# Keyglove_Kit_v0_2.net
KiCad netlist of a schematic drawn in EAGLE
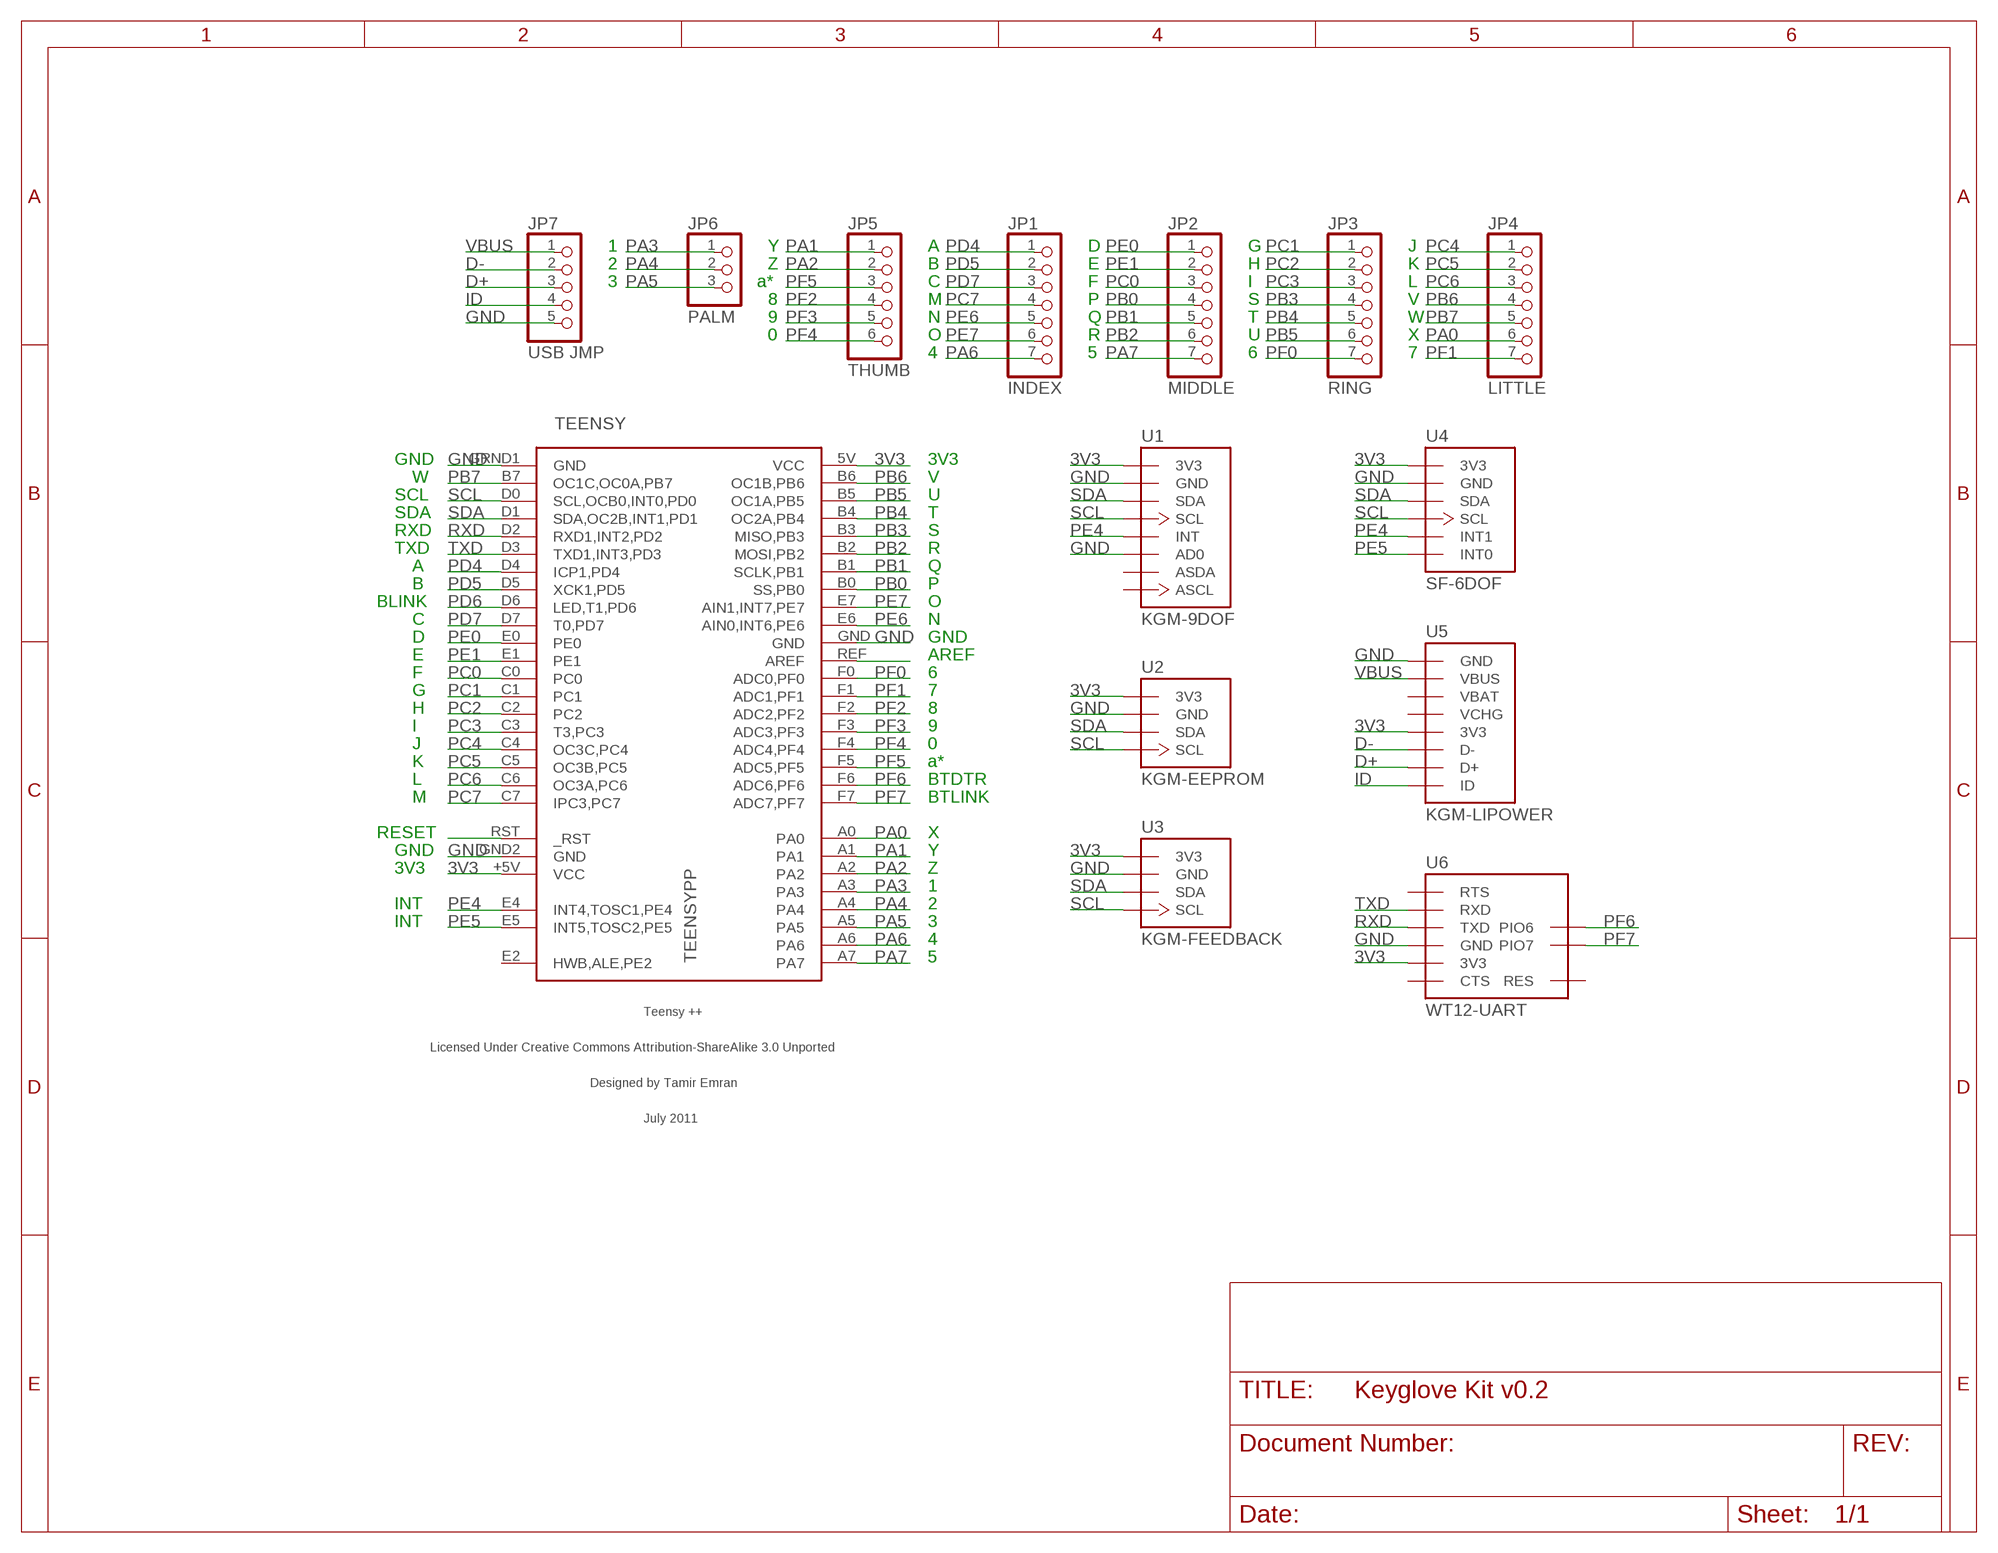
[diagram p0: schematic, sheet 1]

(export (version "E")
  (design (tool "Eeschema 10.0.6"))
  (components
    (comp (ref "JP1")
      (value "INDEX")
      (footprint "eagle-import:1X07")
      (libsource (lib "eagle-import") (part "PINHD-1X7"))
    )
    (comp (ref "JP2")
      (value "MIDDLE")
      (footprint "eagle-import:1X07")
      (libsource (lib "eagle-import") (part "PINHD-1X7"))
    )
    (comp (ref "JP3")
      (value "RING")
      (footprint "eagle-import:1X07")
      (libsource (lib "eagle-import") (part "PINHD-1X7"))
    )
    (comp (ref "JP4")
      (value "LITTLE")
      (footprint "eagle-import:1X07")
      (libsource (lib "eagle-import") (part "PINHD-1X7"))
    )
    (comp (ref "JP5")
      (value "THUMB")
      (footprint "eagle-import:1X06")
      (libsource (lib "eagle-import") (part "PINHD-1X6"))
    )
    (comp (ref "JP6")
      (value "PALM")
      (footprint "eagle-import:1X03")
      (libsource (lib "eagle-import") (part "PINHD-1X3"))
    )
    (comp (ref "JP7")
      (value "USB JMP")
      (footprint "eagle-import:1X05")
      (libsource (lib "eagle-import") (part "PINHD-1X5"))
    )
    (comp (ref "TEENSY")
      (value "TEENSYPP")
      (footprint "eagle-import:TEENSYPP")
      (libsource (lib "eagle-import") (part "TEENSYPP"))
    )
    (comp (ref "U1")
      (value "KGM-9DOF")
      (footprint "eagle-import:KGM-9DOF")
      (libsource (lib "eagle-import") (part "KGM-9DOF"))
    )
    (comp (ref "U2")
      (value "KGM-EEPROM")
      (footprint "eagle-import:KGM-EEPROM")
      (libsource (lib "eagle-import") (part "KGM-EEPROM"))
    )
    (comp (ref "U3")
      (value "KGM-FEEDBACK")
      (footprint "eagle-import:KGM-FEEDBACK")
      (libsource (lib "eagle-import") (part "KGM-FEEDBACK"))
    )
    (comp (ref "U4")
      (value "SF-6DOF")
      (footprint "eagle-import:SF-6DOF")
      (libsource (lib "eagle-import") (part "SF-6DOF"))
    )
    (comp (ref "U5")
      (value "KGM-LIPOWER")
      (footprint "eagle-import:KGM-LIPOWER")
      (libsource (lib "eagle-import") (part "KGM-LIPOWER"))
    )
    (comp (ref "U6")
      (value "WT12-UART")
      (footprint "eagle-import:WT12-UART")
      (libsource (lib "eagle-import") (part "WT12-UART"))
    )
  )
  (nets
    (net (code "1") (name "/3V3") (class "Default")
      (node (ref "TEENSY") (pin "+5V") (pinfunction "VCC_+5V") (pintype "power_in"))
      (node (ref "TEENSY") (pin "5V") (pinfunction "VCC_5V") (pintype "power_in"))
      (node (ref "U1") (pin "3V3") (pinfunction "3V3_3V3") (pintype "power_in"))
      (node (ref "U2") (pin "3V3") (pinfunction "3V3_3V3") (pintype "power_in"))
      (node (ref "U3") (pin "3V3") (pinfunction "3V3_3V3") (pintype "power_in"))
      (node (ref "U4") (pin "3V3") (pinfunction "3V3_3V3") (pintype "power_in"))
      (node (ref "U5") (pin "3V3") (pinfunction "3V3_3V3") (pintype "power_in"))
      (node (ref "U6") (pin "3V3") (pinfunction "3V3_3V3") (pintype "power_in"))
    )
    (net (code "2") (name "/D+") (class "Default")
      (node (ref "JP7") (pin "3") (pinfunction "3_3") (pintype "passive"))
      (node (ref "U5") (pin "D+") (pinfunction "D+_D+") (pintype "bidirectional"))
    )
    (net (code "3") (name "/D-") (class "Default")
      (node (ref "JP7") (pin "2") (pinfunction "2_2") (pintype "passive"))
      (node (ref "U5") (pin "D-") (pinfunction "D-_D-") (pintype "bidirectional"))
    )
    (net (code "4") (name "/GND") (class "Default")
      (node (ref "JP7") (pin "5") (pinfunction "5_5") (pintype "passive"))
      (node (ref "TEENSY") (pin "GND") (pinfunction "GND_GND") (pintype "power_in"))
      (node (ref "TEENSY") (pin "GND2") (pinfunction "GND_GND2") (pintype "power_in"))
      (node (ref "TEENSY") (pin "GRND1") (pinfunction "GND_GRND1") (pintype "power_in"))
      (node (ref "U1") (pin "AD0") (pinfunction "AD0_AD0") (pintype "input"))
      (node (ref "U1") (pin "GND") (pinfunction "GND_GND") (pintype "power_in"))
      (node (ref "U2") (pin "GND") (pinfunction "GND_GND") (pintype "power_in"))
      (node (ref "U3") (pin "GND") (pinfunction "GND_GND") (pintype "power_in"))
      (node (ref "U4") (pin "GND") (pinfunction "GND_GND") (pintype "power_in"))
      (node (ref "U5") (pin "GND") (pinfunction "GND_GND") (pintype "power_in"))
      (node (ref "U6") (pin "GND") (pinfunction "GND_GND") (pintype "power_in"))
    )
    (net (code "5") (name "/ID") (class "Default")
      (node (ref "JP7") (pin "4") (pinfunction "4_4") (pintype "passive"))
      (node (ref "U5") (pin "ID") (pinfunction "ID_ID") (pintype "bidirectional"))
    )
    (net (code "6") (name "/PA0") (class "Default")
      (node (ref "JP4") (pin "6") (pinfunction "6_6") (pintype "passive"))
      (node (ref "TEENSY") (pin "A0") (pinfunction "PA0_A0") (pintype "bidirectional"))
    )
    (net (code "7") (name "/PA1") (class "Default")
      (node (ref "JP5") (pin "1") (pinfunction "1_1") (pintype "passive"))
      (node (ref "TEENSY") (pin "A1") (pinfunction "PA1_A1") (pintype "bidirectional"))
    )
    (net (code "8") (name "/PA2") (class "Default")
      (node (ref "JP5") (pin "2") (pinfunction "2_2") (pintype "passive"))
      (node (ref "TEENSY") (pin "A2") (pinfunction "PA2_A2") (pintype "bidirectional"))
    )
    (net (code "9") (name "/PA3") (class "Default")
      (node (ref "JP6") (pin "1") (pinfunction "1_1") (pintype "passive"))
      (node (ref "TEENSY") (pin "A3") (pinfunction "PA3_A3") (pintype "bidirectional"))
    )
    (net (code "10") (name "/PA4") (class "Default")
      (node (ref "JP6") (pin "2") (pinfunction "2_2") (pintype "passive"))
      (node (ref "TEENSY") (pin "A4") (pinfunction "PA4_A4") (pintype "bidirectional"))
    )
    (net (code "11") (name "/PA5") (class "Default")
      (node (ref "JP6") (pin "3") (pinfunction "3_3") (pintype "passive"))
      (node (ref "TEENSY") (pin "A5") (pinfunction "PA5_A5") (pintype "bidirectional"))
    )
    (net (code "12") (name "/PA6") (class "Default")
      (node (ref "JP1") (pin "7") (pinfunction "7_7") (pintype "passive"))
      (node (ref "TEENSY") (pin "A6") (pinfunction "PA6_A6") (pintype "bidirectional"))
    )
    (net (code "13") (name "/PA7") (class "Default")
      (node (ref "JP2") (pin "7") (pinfunction "7_7") (pintype "passive"))
      (node (ref "TEENSY") (pin "A7") (pinfunction "PA7_A7") (pintype "bidirectional"))
    )
    (net (code "14") (name "/PB0") (class "Default")
      (node (ref "JP2") (pin "4") (pinfunction "4_4") (pintype "passive"))
      (node (ref "TEENSY") (pin "B0") (pinfunction "SS,PB0_B0") (pintype "bidirectional"))
    )
    (net (code "15") (name "/PB1") (class "Default")
      (node (ref "JP2") (pin "5") (pinfunction "5_5") (pintype "passive"))
      (node (ref "TEENSY") (pin "B1") (pinfunction "SCLK,PB1_B1") (pintype "bidirectional"))
    )
    (net (code "16") (name "/PB2") (class "Default")
      (node (ref "JP2") (pin "6") (pinfunction "6_6") (pintype "passive"))
      (node (ref "TEENSY") (pin "B2") (pinfunction "MOSI,PB2_B2") (pintype "bidirectional"))
    )
    (net (code "17") (name "/PB3") (class "Default")
      (node (ref "JP3") (pin "4") (pinfunction "4_4") (pintype "passive"))
      (node (ref "TEENSY") (pin "B3") (pinfunction "MISO,PB3_B3") (pintype "bidirectional"))
    )
    (net (code "18") (name "/PB4") (class "Default")
      (node (ref "JP3") (pin "5") (pinfunction "5_5") (pintype "passive"))
      (node (ref "TEENSY") (pin "B4") (pinfunction "OC2A,PB4_B4") (pintype "bidirectional"))
    )
    (net (code "19") (name "/PB5") (class "Default")
      (node (ref "JP3") (pin "6") (pinfunction "6_6") (pintype "passive"))
      (node (ref "TEENSY") (pin "B5") (pinfunction "OC1A,PB5_B5") (pintype "bidirectional"))
    )
    (net (code "20") (name "/PB6") (class "Default")
      (node (ref "JP4") (pin "4") (pinfunction "4_4") (pintype "passive"))
      (node (ref "TEENSY") (pin "B6") (pinfunction "OC1B,PB6_B6") (pintype "bidirectional"))
    )
    (net (code "21") (name "/PB7") (class "Default")
      (node (ref "JP4") (pin "5") (pinfunction "5_5") (pintype "passive"))
      (node (ref "TEENSY") (pin "B7") (pinfunction "OC1C,OC0A,PB7_B7") (pintype "bidirectional"))
    )
    (net (code "22") (name "/PC0") (class "Default")
      (node (ref "JP2") (pin "3") (pinfunction "3_3") (pintype "passive"))
      (node (ref "TEENSY") (pin "C0") (pinfunction "PC0_C0") (pintype "bidirectional"))
    )
    (net (code "23") (name "/PC1") (class "Default")
      (node (ref "JP3") (pin "1") (pinfunction "1_1") (pintype "passive"))
      (node (ref "TEENSY") (pin "C1") (pinfunction "PC1_C1") (pintype "bidirectional"))
    )
    (net (code "24") (name "/PC2") (class "Default")
      (node (ref "JP3") (pin "2") (pinfunction "2_2") (pintype "passive"))
      (node (ref "TEENSY") (pin "C2") (pinfunction "PC2_C2") (pintype "bidirectional"))
    )
    (net (code "25") (name "/PC3") (class "Default")
      (node (ref "JP3") (pin "3") (pinfunction "3_3") (pintype "passive"))
      (node (ref "TEENSY") (pin "C3") (pinfunction "T3,PC3_C3") (pintype "bidirectional"))
    )
    (net (code "26") (name "/PC4") (class "Default")
      (node (ref "JP4") (pin "1") (pinfunction "1_1") (pintype "passive"))
      (node (ref "TEENSY") (pin "C4") (pinfunction "OC3C,PC4_C4") (pintype "bidirectional"))
    )
    (net (code "27") (name "/PC5") (class "Default")
      (node (ref "JP4") (pin "2") (pinfunction "2_2") (pintype "passive"))
      (node (ref "TEENSY") (pin "C5") (pinfunction "OC3B,PC5_C5") (pintype "bidirectional"))
    )
    (net (code "28") (name "/PC6") (class "Default")
      (node (ref "JP4") (pin "3") (pinfunction "3_3") (pintype "passive"))
      (node (ref "TEENSY") (pin "C6") (pinfunction "OC3A,PC6_C6") (pintype "bidirectional"))
    )
    (net (code "29") (name "/PC7") (class "Default")
      (node (ref "JP1") (pin "4") (pinfunction "4_4") (pintype "passive"))
      (node (ref "TEENSY") (pin "C7") (pinfunction "IPC3,PC7_C7") (pintype "bidirectional"))
    )
    (net (code "30") (name "/PD4") (class "Default")
      (node (ref "JP1") (pin "1") (pinfunction "1_1") (pintype "passive"))
      (node (ref "TEENSY") (pin "D4") (pinfunction "ICP1,PD4_D4") (pintype "bidirectional"))
    )
    (net (code "31") (name "/PD5") (class "Default")
      (node (ref "JP1") (pin "2") (pinfunction "2_2") (pintype "passive"))
      (node (ref "TEENSY") (pin "D5") (pinfunction "XCK1,PD5_D5") (pintype "bidirectional"))
    )
    (net (code "32") (name "/PD6") (class "Default")
      (node (ref "TEENSY") (pin "D6") (pinfunction "LED,T1,PD6_D6") (pintype "bidirectional"))
    )
    (net (code "33") (name "/PD7") (class "Default")
      (node (ref "JP1") (pin "3") (pinfunction "3_3") (pintype "passive"))
      (node (ref "TEENSY") (pin "D7") (pinfunction "T0,PD7_D7") (pintype "bidirectional"))
    )
    (net (code "34") (name "/PE0") (class "Default")
      (node (ref "JP2") (pin "1") (pinfunction "1_1") (pintype "passive"))
      (node (ref "TEENSY") (pin "E0") (pinfunction "PE0_E0") (pintype "bidirectional"))
    )
    (net (code "35") (name "/PE1") (class "Default")
      (node (ref "JP2") (pin "2") (pinfunction "2_2") (pintype "passive"))
      (node (ref "TEENSY") (pin "E1") (pinfunction "PE1_E1") (pintype "bidirectional"))
    )
    (net (code "36") (name "/PE4") (class "Default")
      (node (ref "TEENSY") (pin "E4") (pinfunction "INT4,TOSC1,PE4_E4") (pintype "bidirectional"))
      (node (ref "U1") (pin "INT") (pinfunction "INT_INT") (pintype "output"))
      (node (ref "U4") (pin "INT1") (pinfunction "INT1_INT1") (pintype "output"))
    )
    (net (code "37") (name "/PE5") (class "Default")
      (node (ref "TEENSY") (pin "E5") (pinfunction "INT5,TOSC2,PE5_E5") (pintype "bidirectional"))
      (node (ref "U4") (pin "INT0") (pinfunction "INT0_INT0") (pintype "output"))
    )
    (net (code "38") (name "/PE6") (class "Default")
      (node (ref "JP1") (pin "5") (pinfunction "5_5") (pintype "passive"))
      (node (ref "TEENSY") (pin "E6") (pinfunction "AIN0,INT6,PE6_E6") (pintype "bidirectional"))
    )
    (net (code "39") (name "/PE7") (class "Default")
      (node (ref "JP1") (pin "6") (pinfunction "6_6") (pintype "passive"))
      (node (ref "TEENSY") (pin "E7") (pinfunction "AIN1,INT7,PE7_E7") (pintype "bidirectional"))
    )
    (net (code "40") (name "/PF0") (class "Default")
      (node (ref "JP3") (pin "7") (pinfunction "7_7") (pintype "passive"))
      (node (ref "TEENSY") (pin "F0") (pinfunction "ADC0,PF0_F0") (pintype "bidirectional"))
    )
    (net (code "41") (name "/PF1") (class "Default")
      (node (ref "JP4") (pin "7") (pinfunction "7_7") (pintype "passive"))
      (node (ref "TEENSY") (pin "F1") (pinfunction "ADC1,PF1_F1") (pintype "bidirectional"))
    )
    (net (code "42") (name "/PF2") (class "Default")
      (node (ref "JP5") (pin "4") (pinfunction "4_4") (pintype "passive"))
      (node (ref "TEENSY") (pin "F2") (pinfunction "ADC2,PF2_F2") (pintype "bidirectional"))
    )
    (net (code "43") (name "/PF3") (class "Default")
      (node (ref "JP5") (pin "5") (pinfunction "5_5") (pintype "passive"))
      (node (ref "TEENSY") (pin "F3") (pinfunction "ADC3,PF3_F3") (pintype "bidirectional"))
    )
    (net (code "44") (name "/PF4") (class "Default")
      (node (ref "JP5") (pin "6") (pinfunction "6_6") (pintype "passive"))
      (node (ref "TEENSY") (pin "F4") (pinfunction "ADC4,PF4_F4") (pintype "bidirectional"))
    )
    (net (code "45") (name "/PF5") (class "Default")
      (node (ref "JP5") (pin "3") (pinfunction "3_3") (pintype "passive"))
      (node (ref "TEENSY") (pin "F5") (pinfunction "ADC5,PF5_F5") (pintype "bidirectional"))
    )
    (net (code "46") (name "/PF6") (class "Default")
      (node (ref "TEENSY") (pin "F6") (pinfunction "ADC6,PF6_F6") (pintype "bidirectional"))
      (node (ref "U6") (pin "PIO6") (pinfunction "PIO6_PIO6") (pintype "bidirectional"))
    )
    (net (code "47") (name "/PF7") (class "Default")
      (node (ref "TEENSY") (pin "F7") (pinfunction "ADC7,PF7_F7") (pintype "bidirectional"))
      (node (ref "U6") (pin "PIO7") (pinfunction "PIO7_PIO7") (pintype "bidirectional"))
    )
    (net (code "48") (name "/RXD") (class "Default")
      (node (ref "TEENSY") (pin "D2") (pinfunction "RXD1,INT2,PD2_D2") (pintype "bidirectional"))
      (node (ref "U6") (pin "TXD") (pinfunction "TXD_TXD") (pintype "output"))
    )
    (net (code "49") (name "/SCL") (class "Default")
      (node (ref "TEENSY") (pin "D0") (pinfunction "SCL,OCB0,INT0,PD0_D0") (pintype "bidirectional"))
      (node (ref "U1") (pin "SCL") (pinfunction "SCL_SCL") (pintype "bidirectional"))
      (node (ref "U2") (pin "SCL") (pinfunction "SCL_SCL") (pintype "bidirectional"))
      (node (ref "U3") (pin "SCL") (pinfunction "SCL_SCL") (pintype "bidirectional"))
      (node (ref "U4") (pin "SCL") (pinfunction "SCL_SCL") (pintype "bidirectional"))
    )
    (net (code "50") (name "/SDA") (class "Default")
      (node (ref "TEENSY") (pin "D1") (pinfunction "SDA,OC2B,INT1,PD1_D1") (pintype "bidirectional"))
      (node (ref "U1") (pin "SDA") (pinfunction "SDA_SDA") (pintype "bidirectional"))
      (node (ref "U2") (pin "SDA") (pinfunction "SDA_SDA") (pintype "bidirectional"))
      (node (ref "U3") (pin "SDA") (pinfunction "SDA_SDA") (pintype "bidirectional"))
      (node (ref "U4") (pin "SDA") (pinfunction "SDA_SDA") (pintype "bidirectional"))
    )
    (net (code "51") (name "/TXD") (class "Default")
      (node (ref "TEENSY") (pin "D3") (pinfunction "TXD1,INT3,PD3_D3") (pintype "bidirectional"))
      (node (ref "U6") (pin "RXD") (pinfunction "RXD_RXD") (pintype "input"))
    )
    (net (code "52") (name "/VBAT") (class "Default")
      (node (ref "U5") (pin "VBAT") (pinfunction "VBAT_VBAT") (pintype "power_in"))
    )
    (net (code "53") (name "/VBUS") (class "Default")
      (node (ref "JP7") (pin "1") (pinfunction "1_1") (pintype "passive"))
      (node (ref "U5") (pin "VBUS") (pinfunction "VBUS_VBUS") (pintype "power_in"))
    )
    (net (code "54") (name "/VCHG") (class "Default")
      (node (ref "U5") (pin "VCHG") (pinfunction "VCHG_VCHG") (pintype "power_in"))
    )
    (net (code "55") (name "unconnected-(TEENSY-AREF-PadREF)") (class "Default")
      (node (ref "TEENSY") (pin "REF") (pinfunction "AREF_REF") (pintype "input"))
    )
    (net (code "56") (name "unconnected-(TEENSY-HWB,ALE,PE2-PadE2)") (class "Default")
      (node (ref "TEENSY") (pin "E2") (pinfunction "HWB,ALE,PE2_E2") (pintype "bidirectional"))
    )
    (net (code "57") (name "unconnected-(TEENSY-_RST-PadRST)") (class "Default")
      (node (ref "TEENSY") (pin "RST") (pinfunction "_RST_RST") (pintype "input"))
    )
    (net (code "58") (name "unconnected-(U1-PadASCL)") (class "Default")
      (node (ref "U1") (pin "ASCL") (pinfunction "ASCL_ASCL") (pintype "bidirectional"))
    )
    (net (code "59") (name "unconnected-(U1-PadASDA)") (class "Default")
      (node (ref "U1") (pin "ASDA") (pinfunction "ASDA_ASDA") (pintype "bidirectional"))
    )
    (net (code "60") (name "unconnected-(U6-PadCTS)") (class "Default")
      (node (ref "U6") (pin "CTS") (pinfunction "CTS_CTS") (pintype "input"))
    )
    (net (code "61") (name "unconnected-(U6-PadRTS)") (class "Default")
      (node (ref "U6") (pin "RTS") (pinfunction "RTS_RTS") (pintype "output"))
    )
    (net (code "62") (name "unconnected-(U6-RES-PadRESET)") (class "Default")
      (node (ref "U6") (pin "RESET") (pinfunction "RES_RESET") (pintype "input"))
    )
  )
)
